# NB992F_XL_N76E003_MAIN.net
KiCad netlist of a schematic drawn in Altium Designer
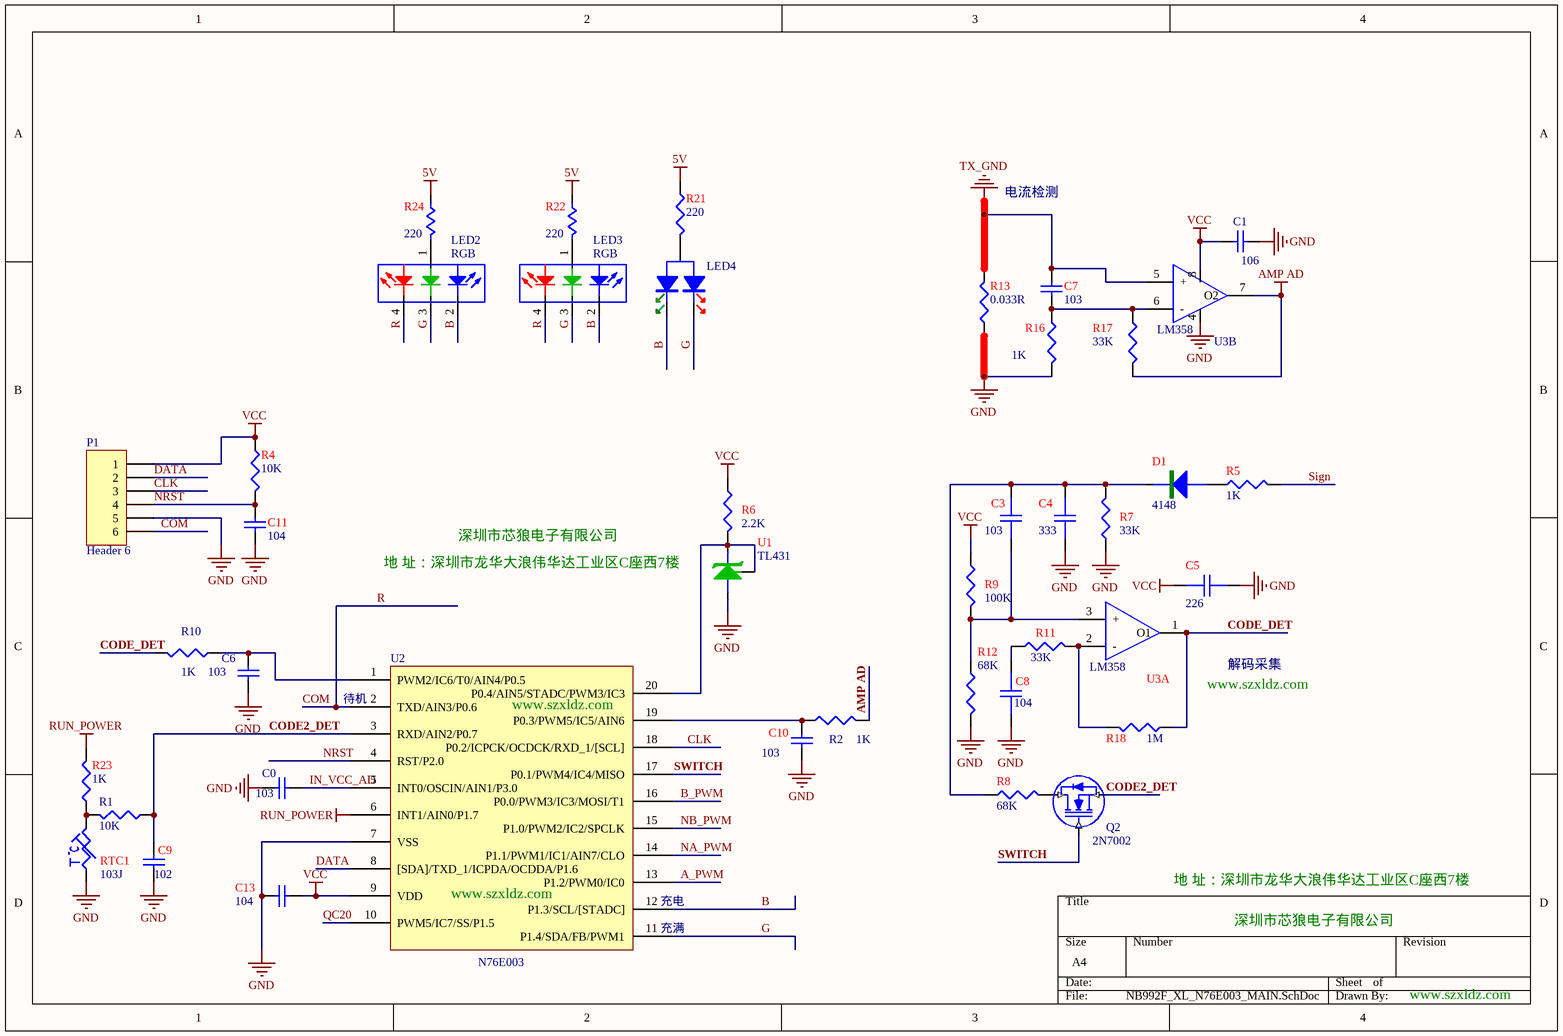
[diagram p0: NB992F_XL_N76E003_MAIN.SchDoc]

(export (version "E")
  (design (tool "Eeschema 10.0.6"))
  (components
    (comp (ref "C0")
      (value "103")
      (footprint "C0402")
      (description "Capacitor")
      (fields (field (name "PUBLISHER") "Altium Limited"))
      (libsource (lib "*") (part "Cap"))
    )
    (comp (ref "C1")
      (value "106")
      (footprint "C0603")
      (description "Capacitor")
      (fields (field (name "PUBLISHER") "Altium Limited"))
      (libsource (lib "*") (part "Cap"))
    )
    (comp (ref "C3") (value "103") (footprint "C0402") (libsource (lib "*") (part "CH")))
    (comp (ref "C4") (value "333") (footprint "C0402") (libsource (lib "*") (part "CH")))
    (comp (ref "C5") (value "226") (footprint "C0805") (libsource (lib "*") (part "CH")))
    (comp (ref "C6")
      (value "103")
      (footprint "C0402")
      (description "Capacitor")
      (fields (field (name "PUBLISHER") "Altium Limited"))
      (libsource (lib "*") (part "Cap"))
    )
    (comp (ref "C7")
      (value "103")
      (footprint "C0402")
      (description "Capacitor")
      (fields (field (name "PUBLISHER") "Altium Limited"))
      (libsource (lib "*") (part "Cap"))
    )
    (comp (ref "C8") (value "104") (footprint "C0402") (libsource (lib "*") (part "CH")))
    (comp (ref "C9")
      (value "102")
      (footprint "C0402")
      (description "Capacitor")
      (fields (field (name "PUBLISHER") "Altium Limited"))
      (libsource (lib "*") (part "Cap"))
    )
    (comp (ref "C10")
      (value "103")
      (footprint "C0402")
      (description "Capacitor")
      (fields (field (name "PUBLISHER") "Altium Limited"))
      (libsource (lib "*") (part "Cap"))
    )
    (comp (ref "C11")
      (value "104")
      (footprint "C0402")
      (description "Capacitor")
      (fields (field (name "PUBLISHER") "Altium Limited"))
      (libsource (lib "*") (part "Cap"))
    )
    (comp (ref "C13")
      (value "104")
      (footprint "C0402")
      (description "Capacitor")
      (fields (field (name "PUBLISHER") "Altium Limited"))
      (libsource (lib "*") (part "Cap"))
    )
    (comp (ref "D1")
      (value "4148")
      (footprint "sod323")
      (description "1N4001")
      (libsource (lib "*") (part "D0"))
    )
    (comp (ref "LED2") (value "RGB") (footprint "LED-RGB02") (libsource (lib "XiaoQiang") (part "LED05")))
    (comp (ref "LED3") (value "RGB") (footprint "LED-RGB02") (libsource (lib "XiaoQiang") (part "LED05")))
    (comp (ref "LED4") (value "~") (footprint "LED2") (libsource (lib "lxzschlib") (part "LED2A")))
    (comp (ref "P1")
      (value "Header 6")
      (footprint "SPIN6")
      (description "Header, 6-Pin")
      (fields (field (name "PUBLISHER") "Altium Limited"))
      (libsource (lib "Miscellaneous Connectors") (part "Header 6"))
    )
    (comp (ref "Q2") (value "2N7002") (footprint "SOT-23B") (libsource (lib "lxzschlib") (part "MOSFETN")))
    (comp (ref "R1")
      (value "10K")
      (footprint "R0402")
      (description "1K")
      (libsource (lib "lxzschlib") (part "R"))
    )
    (comp (ref "R2") (value "1K") (footprint "R0402") (libsource (lib "*") (part "R")))
    (comp (ref "R4") (value "10K") (footprint "R0402") (libsource (lib "*") (part "R")))
    (comp (ref "R5") (value "1K") (footprint "R0402") (libsource (lib "*") (part "R")))
    (comp (ref "R6") (value "2.2K") (footprint "R0402") (description "1K") (libsource (lib "*") (part "R")))
    (comp (ref "R7") (value "33K") (footprint "R0402") (description "1K") (libsource (lib "*") (part "R")))
    (comp (ref "R8") (value "68K") (footprint "R0402") (description "1K") (libsource (lib "*") (part "R")))
    (comp (ref "R9") (value "100K") (footprint "R0402") (description "1K") (libsource (lib "*") (part "R")))
    (comp (ref "R10") (value "1K") (footprint "R0402") (libsource (lib "*") (part "R")))
    (comp (ref "R11") (value "33K") (footprint "R0402") (description "1K") (libsource (lib "*") (part "R")))
    (comp (ref "R12") (value "68K") (footprint "R0402") (description "1K") (libsource (lib "*") (part "R")))
    (comp (ref "R13")
      (value "0.033R")
      (footprint "R0805")
      (description "1K")
      (libsource (lib "*") (part "R"))
    )
    (comp (ref "R16") (value "1K") (footprint "R0402") (libsource (lib "*") (part "R")))
    (comp (ref "R17") (value "33K") (footprint "R0402") (description "1K") (libsource (lib "*") (part "R")))
    (comp (ref "R18") (value "1M") (footprint "R0402") (description "1K") (libsource (lib "*") (part "R")))
    (comp (ref "R21") (value "220") (footprint "R0402") (description "1K") (libsource (lib "*") (part "R")))
    (comp (ref "R22") (value "220") (footprint "R0402") (libsource (lib "XiaoQiang") (part "Res01")))
    (comp (ref "R23") (value "1K") (footprint "R0402") (libsource (lib "lxzschlib") (part "R")))
    (comp (ref "R24") (value "220") (footprint "R0402") (libsource (lib "XiaoQiang") (part "Res01")))
    (comp (ref "RTC1") (value "103J") (footprint "R0402") (libsource (lib "lxzschlib") (part "RTC")))
    (comp (ref "U1")
      (value "TL431")
      (footprint "SOT-23A")
      (description "IC")
      (libsource (lib "lxzschlib") (part "IC TL431"))
    )
    (comp (ref "U2") (value "N76E003") (footprint "TSSOP20") (libsource (lib "BEE802_V11") (part "103F")))
    (comp (ref "U3") (value "LM358") (footprint "SOP8") (libsource (lib "lxzschlib") (part "4558")))
  )
  (nets
    (net (code "1") (name "/A_PWM") (class "Default")
      (node (ref "U2") (pin "13") (pinfunction "P1.2/PWM0/IC0_13") (pintype "passive"))
    )
    (net (code "2") (name "/B") (class "Default")
      (node (ref "LED2") (pin "2") (pinfunction "A_2") (pintype "passive"))
      (node (ref "LED3") (pin "2") (pinfunction "A_2") (pintype "passive"))
      (node (ref "LED4") (pin "3") (pintype "passive"))
      (node (ref "U2") (pin "12") (pinfunction "P1.3/SCL/[STADC]_12") (pintype "passive"))
    )
    (net (code "3") (name "/B_PWM") (class "Default")
      (node (ref "U2") (pin "16") (pinfunction "P0.0/PWM3/IC3/MOSI/T1_16") (pintype "passive"))
    )
    (net (code "4") (name "/CLK") (class "Default")
      (node (ref "P1") (pin "3") (pinfunction "3_3") (pintype "passive"))
      (node (ref "U2") (pin "18") (pinfunction "P0.2/ICPCK/OCDCK/RXD_1/[SCL]_18") (pintype "passive"))
    )
    (net (code "5") (name "/CODE2_DET") (class "Default")
      (node (ref "C9") (pin "2") (pinfunction "2_2") (pintype "passive"))
      (node (ref "Q2") (pin "E") (pinfunction "S_E") (pintype "input"))
      (node (ref "R1") (pin "1") (pintype "passive"))
      (node (ref "U2") (pin "3") (pinfunction "RXD/AIN2/P0.7_3") (pintype "passive"))
    )
    (net (code "6") (name "/CODE_DET") (class "Default")
      (node (ref "R10") (pin "2") (pintype "passive"))
      (node (ref "R18") (pin "1") (pintype "passive"))
      (node (ref "U3") (pin "1") (pinfunction "O1_1") (pintype "passive"))
    )
    (net (code "7") (name "/COM") (class "Default")
      (node (ref "LED2") (pin "4") (pinfunction "2_4") (pintype "passive"))
      (node (ref "LED3") (pin "4") (pinfunction "2_4") (pintype "passive"))
      (node (ref "P1") (pin "6") (pinfunction "6_6") (pintype "passive"))
      (node (ref "U2") (pin "2") (pinfunction "TXD/AIN3/P0.6_2") (pintype "passive"))
    )
    (net (code "8") (name "/DATA") (class "Default")
      (node (ref "P1") (pin "2") (pinfunction "2_2") (pintype "passive"))
      (node (ref "U2") (pin "8") (pinfunction "[SDA]/TXD_1/ICPDA/OCDDA/P1.6_8") (pintype "passive"))
    )
    (net (code "9") (name "/G") (class "Default")
      (node (ref "LED2") (pin "3") (pinfunction "2_3") (pintype "passive"))
      (node (ref "LED3") (pin "3") (pinfunction "2_3") (pintype "passive"))
      (node (ref "LED4") (pin "1") (pintype "passive"))
      (node (ref "U2") (pin "11") (pinfunction "P1.4/SDA/FB/PWM1_11") (pintype "passive"))
    )
    (net (code "10") (name "/IN_VCC_AD") (class "Default")
      (node (ref "C0") (pin "2") (pinfunction "2_2") (pintype "passive"))
      (node (ref "U2") (pin "5") (pinfunction "INT0/OSCIN/AIN1/P3.0_5") (pintype "passive"))
    )
    (net (code "11") (name "/NA_PWM") (class "Default")
      (node (ref "U2") (pin "14") (pinfunction "P1.1/PWM1/IC1/AIN7/CLO_14") (pintype "passive"))
    )
    (net (code "12") (name "/NB_PWM") (class "Default")
      (node (ref "U2") (pin "15") (pinfunction "P1.0/PWM2/IC2/SPCLK_15") (pintype "passive"))
    )
    (net (code "13") (name "/NRST") (class "Default")
      (node (ref "C11") (pin "1") (pinfunction "1_1") (pintype "passive"))
      (node (ref "P1") (pin "4") (pinfunction "4_4") (pintype "passive"))
      (node (ref "R4") (pin "2") (pintype "passive"))
      (node (ref "U2") (pin "4") (pinfunction "RST/P2.0_4") (pintype "passive"))
    )
    (net (code "14") (name "/QC20") (class "Default")
      (node (ref "U2") (pin "10") (pinfunction "PWM5/IC7/SS/P1.5_10") (pintype "passive"))
    )
    (net (code "15") (name "/SWITCH") (class "Default")
      (node (ref "Q2") (pin "B") (pinfunction "G_B") (pintype "input"))
      (node (ref "U2") (pin "17") (pinfunction "P0.1/PWM4/IC4/MISO_17") (pintype "passive"))
    )
    (net (code "16") (name "/Sign") (class "Default") (node (ref "R5") (pin "2") (pintype "passive")))
    (net (code "17") (name "5V") (class "Default")
      (node (ref "R21") (pin "1") (pintype "passive"))
      (node (ref "R22") (pin "1") (pinfunction "1_1") (pintype "passive"))
      (node (ref "R24") (pin "1") (pinfunction "1_1") (pintype "passive"))
    )
    (net (code "18") (name "AMP AD") (class "Default")
      (node (ref "R17") (pin "2") (pintype "passive"))
      (node (ref "R2") (pin "2") (pintype "passive"))
      (node (ref "U3") (pin "7") (pinfunction "O2_7") (pintype "passive"))
    )
    (net (code "19") (name "GND") (class "Default")
      (node (ref "C0") (pin "1") (pinfunction "1_1") (pintype "passive"))
      (node (ref "C1") (pin "1") (pinfunction "1_1") (pintype "passive"))
      (node (ref "C10") (pin "2") (pinfunction "2_2") (pintype "passive"))
      (node (ref "C11") (pin "2") (pinfunction "2_2") (pintype "passive"))
      (node (ref "C13") (pin "1") (pinfunction "1_1") (pintype "passive"))
      (node (ref "C4") (pin "1") (pintype "passive"))
      (node (ref "C5") (pin "1") (pintype "passive"))
      (node (ref "C6") (pin "1") (pinfunction "1_1") (pintype "passive"))
      (node (ref "C8") (pin "1") (pintype "passive"))
      (node (ref "C9") (pin "1") (pinfunction "1_1") (pintype "passive"))
      (node (ref "P1") (pin "5") (pinfunction "5_5") (pintype "passive"))
      (node (ref "R12") (pin "2") (pintype "passive"))
      (node (ref "R13") (pin "1") (pintype "passive"))
      (node (ref "R16") (pin "2") (pintype "passive"))
      (node (ref "R7") (pin "1") (pintype "passive"))
      (node (ref "RTC1") (pin "1") (pintype "passive"))
      (node (ref "U1") (pin "1") (pintype "passive"))
      (node (ref "U2") (pin "7") (pinfunction "VSS_7") (pintype "passive"))
      (node (ref "U3") (pin "4") (pintype "passive"))
    )
    (net (code "20") (name "Net-(C3-Pad1)") (class "Default")
      (node (ref "C3") (pin "1") (pintype "passive"))
      (node (ref "C4") (pin "2") (pintype "passive"))
      (node (ref "D1") (pin "2") (pintype "passive"))
      (node (ref "R7") (pin "2") (pintype "passive"))
      (node (ref "R8") (pin "1") (pintype "passive"))
    )
    (net (code "21") (name "Net-(C8-Pad2)") (class "Default")
      (node (ref "C8") (pin "2") (pintype "passive"))
      (node (ref "R11") (pin "1") (pintype "passive"))
    )
    (net (code "22") (name "Net-(D1-Pad1)") (class "Default")
      (node (ref "D1") (pin "1") (pintype "passive"))
      (node (ref "R5") (pin "1") (pintype "passive"))
    )
    (net (code "23") (name "Net-(LED2-A-Pad1)") (class "Default")
      (node (ref "LED2") (pin "1") (pinfunction "A_1") (pintype "passive"))
      (node (ref "R24") (pin "2") (pinfunction "2_2") (pintype "passive"))
    )
    (net (code "24") (name "Net-(LED3-A-Pad1)") (class "Default")
      (node (ref "LED3") (pin "1") (pinfunction "A_1") (pintype "passive"))
      (node (ref "R22") (pin "2") (pinfunction "2_2") (pintype "passive"))
    )
    (net (code "25") (name "Net-(LED4-Pad2)") (class "Default")
      (node (ref "LED4") (pin "2") (pintype "passive"))
      (node (ref "R21") (pin "2") (pintype "passive"))
    )
    (net (code "26") (name "Net-(Q2-D)") (class "Default")
      (node (ref "Q2") (pin "C") (pinfunction "D_C") (pintype "input"))
      (node (ref "R8") (pin "2") (pintype "passive"))
    )
    (net (code "27") (name "Net-(R1-Pad2)") (class "Default")
      (node (ref "R1") (pin "2") (pintype "passive"))
      (node (ref "R23") (pin "1") (pintype "passive"))
      (node (ref "RTC1") (pin "2") (pintype "passive"))
    )
    (net (code "28") (name "Net-(U2-P0.3{slash}PWM5{slash}IC5{slash}AIN6)") (class "Default")
      (node (ref "C10") (pin "1") (pinfunction "1_1") (pintype "passive"))
      (node (ref "R2") (pin "1") (pintype "passive"))
      (node (ref "U2") (pin "19") (pinfunction "P0.3/PWM5/IC5/AIN6_19") (pintype "passive"))
    )
    (net (code "29") (name "Net-(U2-P0.4{slash}AIN5{slash}STADC{slash}PWM3{slash}IC3)") (class "Default")
      (node (ref "R6") (pin "2") (pintype "passive"))
      (node (ref "U1") (pin "2") (pintype "passive"))
      (node (ref "U1") (pin "3") (pintype "passive"))
      (node (ref "U2") (pin "20") (pinfunction "P0.4/AIN5/STADC/PWM3/IC3_20") (pintype "passive"))
    )
    (net (code "30") (name "Net-(U2-PWM2{slash}IC6{slash}T0{slash}AIN4{slash}P0.5)") (class "Default")
      (node (ref "C6") (pin "2") (pinfunction "2_2") (pintype "passive"))
      (node (ref "R10") (pin "1") (pintype "passive"))
      (node (ref "U2") (pin "1") (pinfunction "PWM2/IC6/T0/AIN4/P0.5_1") (pintype "passive"))
    )
    (net (code "31") (name "Net-(U3A-+)") (class "Default")
      (node (ref "C3") (pin "2") (pintype "passive"))
      (node (ref "R12") (pin "1") (pintype "passive"))
      (node (ref "R9") (pin "2") (pintype "passive"))
      (node (ref "U3") (pin "3") (pinfunction "+_3") (pintype "passive"))
    )
    (net (code "32") (name "Net-(U3A--)") (class "Default")
      (node (ref "R11") (pin "2") (pintype "passive"))
      (node (ref "R18") (pin "2") (pintype "passive"))
      (node (ref "U3") (pin "2") (pinfunction "-_2") (pintype "passive"))
    )
    (net (code "33") (name "Net-(U3B--)") (class "Default")
      (node (ref "C7") (pin "2") (pinfunction "2_2") (pintype "passive"))
      (node (ref "R16") (pin "1") (pintype "passive"))
      (node (ref "R17") (pin "1") (pintype "passive"))
      (node (ref "U3") (pin "6") (pinfunction "-_6") (pintype "passive"))
    )
    (net (code "34") (name "RUN_POWER") (class "Default")
      (node (ref "R23") (pin "2") (pintype "passive"))
      (node (ref "U2") (pin "6") (pinfunction "INT1/AIN0/P1.7_6") (pintype "passive"))
    )
    (net (code "35") (name "TX_GND") (class "Default")
      (node (ref "C7") (pin "1") (pinfunction "1_1") (pintype "passive"))
      (node (ref "R13") (pin "2") (pintype "passive"))
      (node (ref "U3") (pin "5") (pinfunction "+_5") (pintype "passive"))
    )
    (net (code "36") (name "VCC") (class "Default")
      (node (ref "C1") (pin "2") (pinfunction "2_2") (pintype "passive"))
      (node (ref "C13") (pin "2") (pinfunction "2_2") (pintype "passive"))
      (node (ref "C5") (pin "2") (pintype "passive"))
      (node (ref "P1") (pin "1") (pinfunction "1_1") (pintype "passive"))
      (node (ref "R4") (pin "1") (pintype "passive"))
      (node (ref "R6") (pin "1") (pintype "passive"))
      (node (ref "R9") (pin "1") (pintype "passive"))
      (node (ref "U2") (pin "9") (pinfunction "VDD_9") (pintype "passive"))
      (node (ref "U3") (pin "8") (pintype "passive"))
    )
  )
)
